# axiom_beta_interface_dummy_v0_9.net
KiCad netlist of a schematic drawn in EAGLE
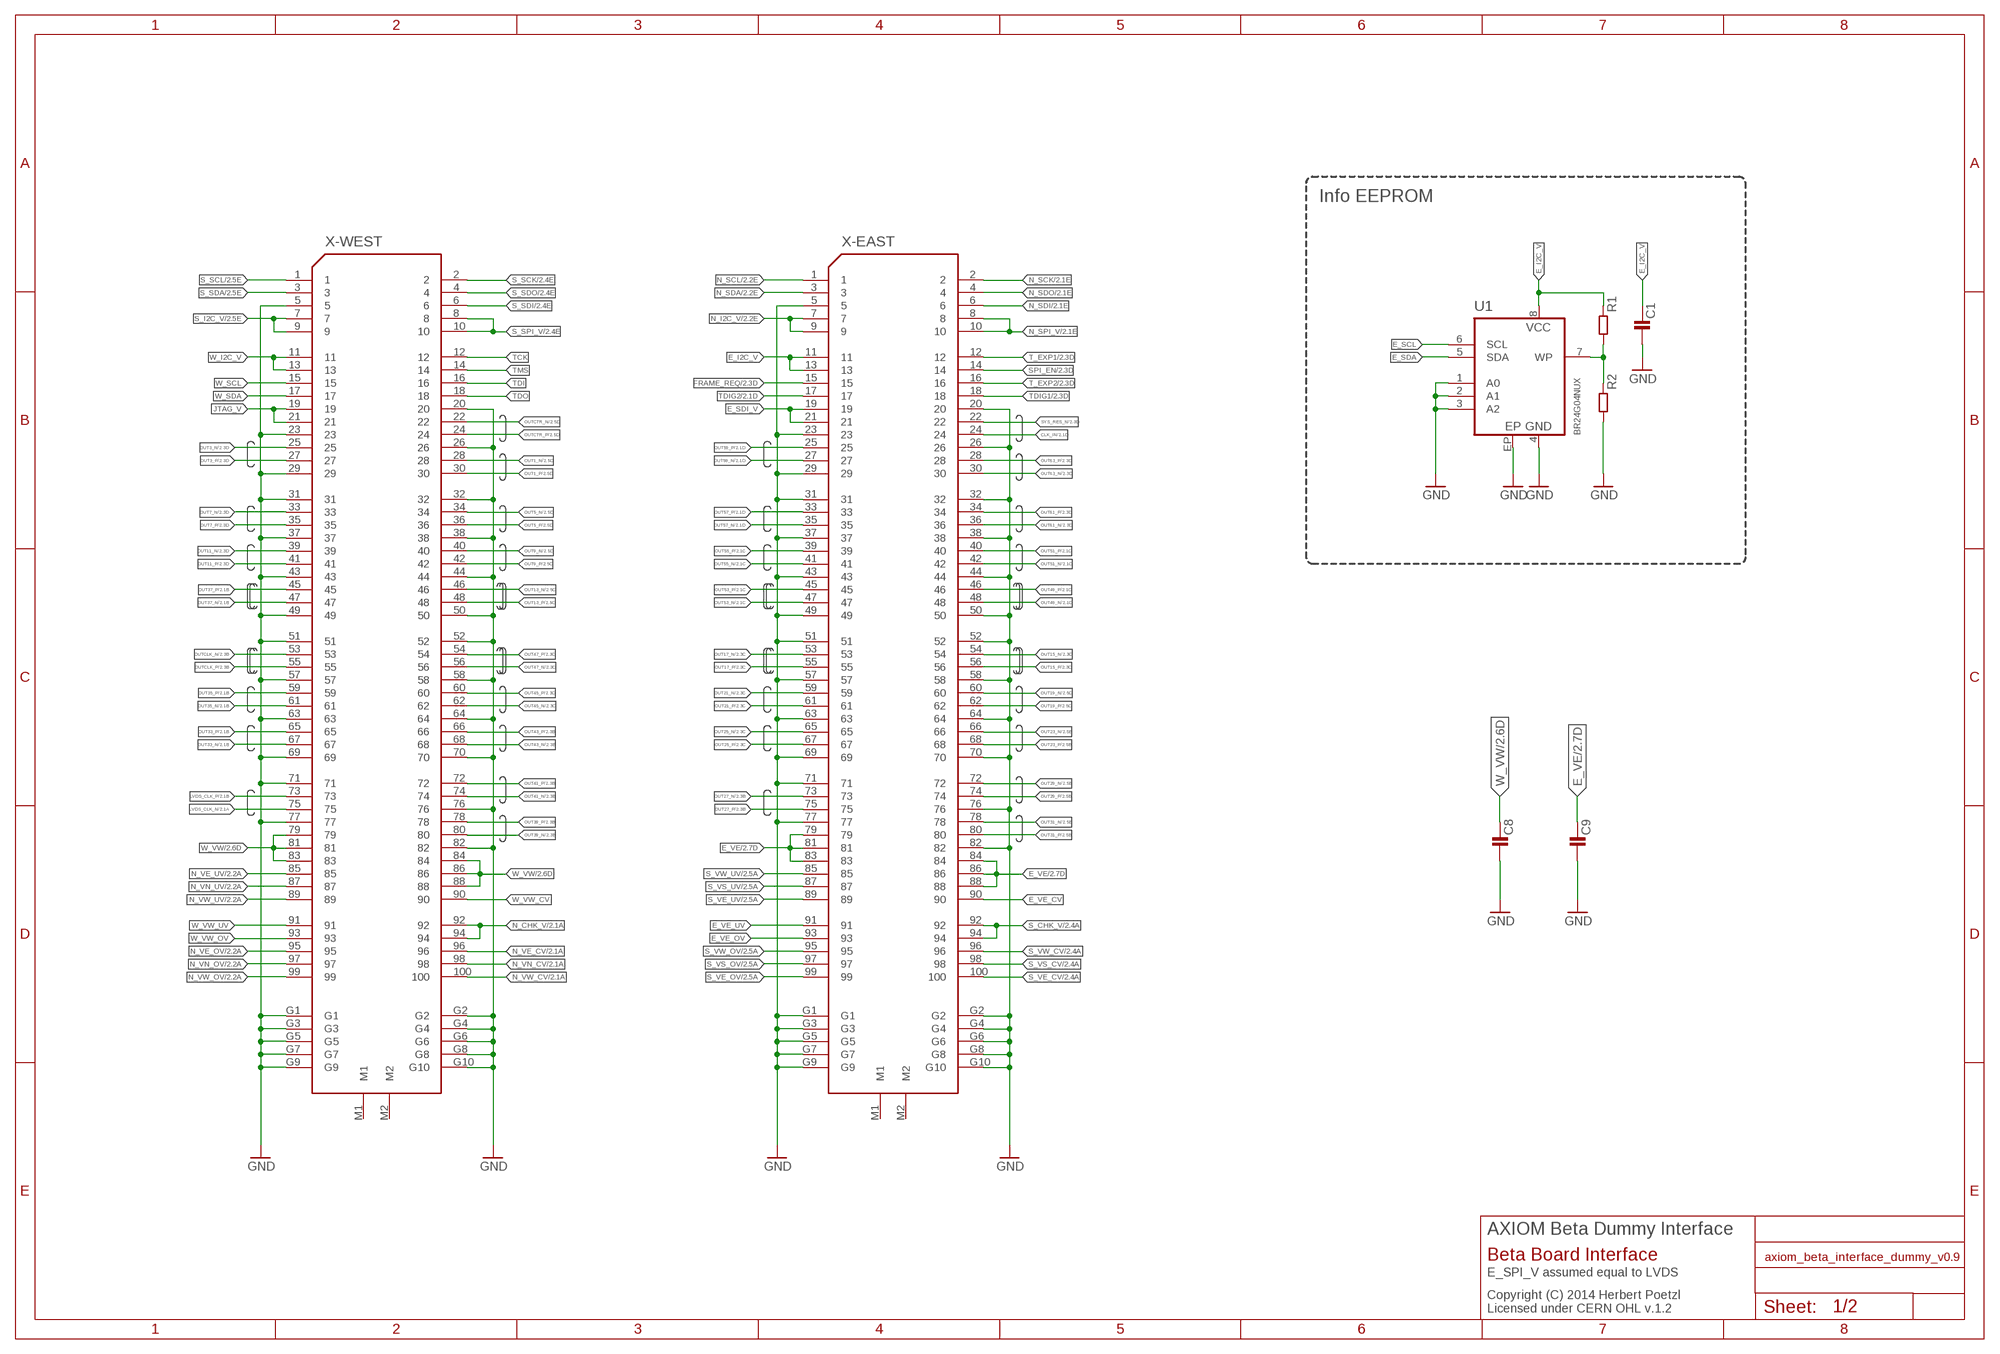
[diagram p0: schematic, sheet 1]
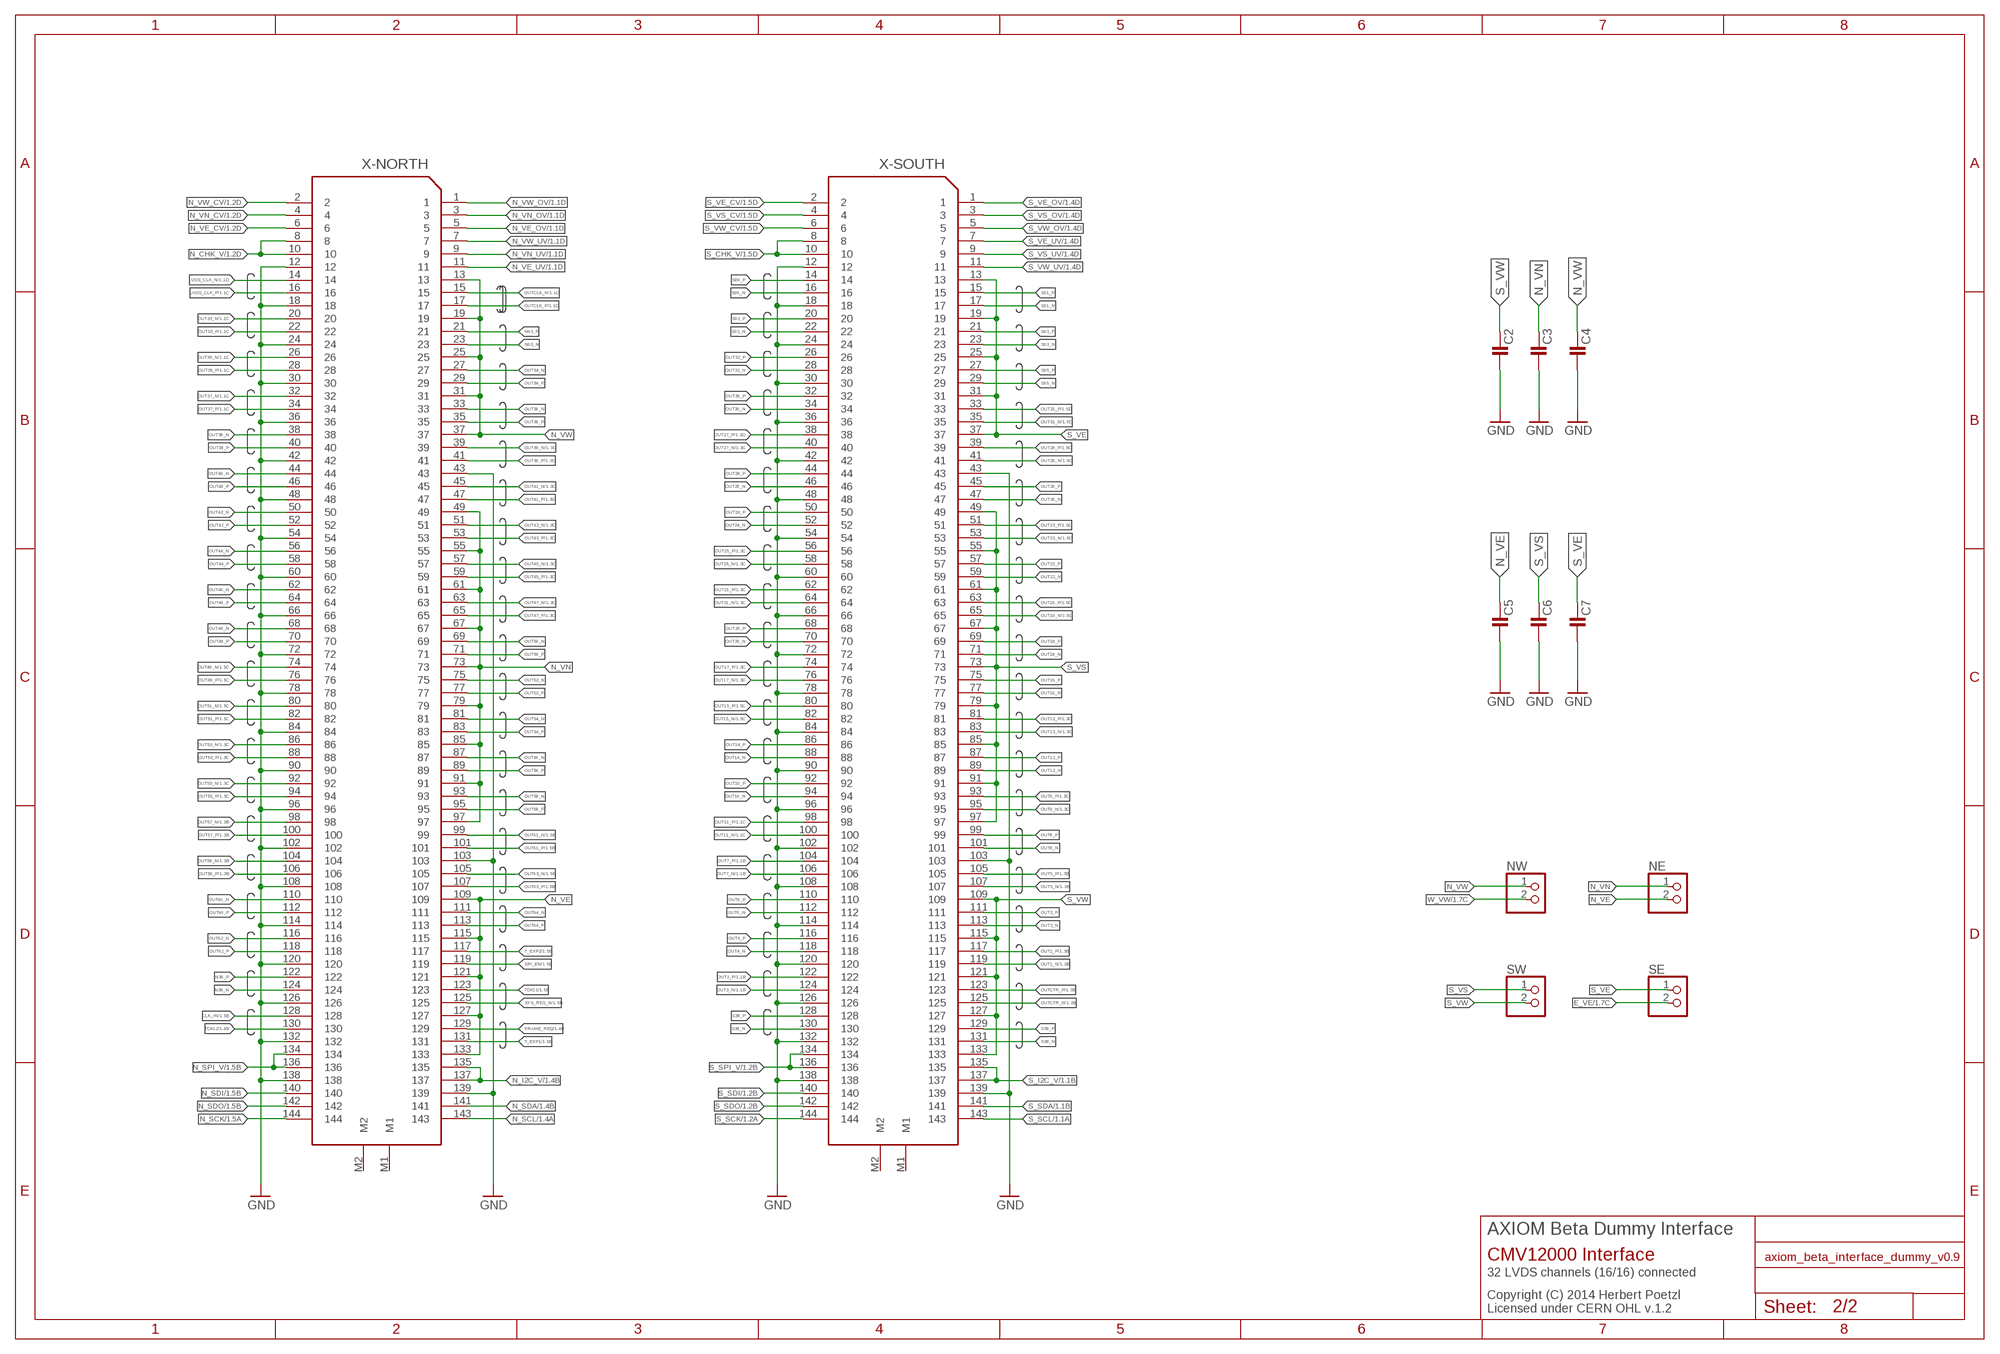
[diagram p1: schematic, sheet 2]

(export (version "E")
  (design (tool "Eeschema 10.0.6"))
  (components
    (comp (ref "C2")
      (value "C0805-B")
      (footprint "eagle-import:0805-B")
      (libsource (lib "eagle-import") (part "C0805-B"))
    )
    (comp (ref "C3")
      (value "C0805-B")
      (footprint "eagle-import:0805-B")
      (libsource (lib "eagle-import") (part "C0805-B"))
    )
    (comp (ref "C4")
      (value "C0805-B")
      (footprint "eagle-import:0805-B")
      (libsource (lib "eagle-import") (part "C0805-B"))
    )
    (comp (ref "C5")
      (value "C0805-B")
      (footprint "eagle-import:0805-B")
      (libsource (lib "eagle-import") (part "C0805-B"))
    )
    (comp (ref "C6")
      (value "C0805-B")
      (footprint "eagle-import:0805-B")
      (libsource (lib "eagle-import") (part "C0805-B"))
    )
    (comp (ref "C7")
      (value "C0805-B")
      (footprint "eagle-import:0805-B")
      (libsource (lib "eagle-import") (part "C0805-B"))
    )
    (comp (ref "NE")
      (value "PINHD-1X02_2.54")
      (footprint "eagle-import:1X02")
      (libsource (lib "eagle-import") (part "PINHD-1X02_2.54"))
    )
    (comp (ref "NW")
      (value "PINHD-1X02_2.54")
      (footprint "eagle-import:1X02")
      (libsource (lib "eagle-import") (part "PINHD-1X02_2.54"))
    )
    (comp (ref "SE")
      (value "PINHD-1X02_2.54")
      (footprint "eagle-import:1X02")
      (libsource (lib "eagle-import") (part "PINHD-1X02_2.54"))
    )
    (comp (ref "SW")
      (value "PINHD-1X02_2.54")
      (footprint "eagle-import:1X02")
      (libsource (lib "eagle-import") (part "PINHD-1X02_2.54"))
    )
    (comp (ref "X-NORTH")
      (value "FX10-144S")
      (footprint "eagle-import:FX10A-144S")
      (libsource (lib "eagle-import") (part "FX10-144S"))
    )
    (comp (ref "X-SOUTH")
      (value "FX10-144S")
      (footprint "eagle-import:FX10A-144S")
      (libsource (lib "eagle-import") (part "FX10-144S"))
    )
    (comp (ref "C1")
      (value "C0402-B")
      (footprint "eagle-import:0402-B")
      (libsource (lib "eagle-import") (part "C0402-B"))
    )
    (comp (ref "C8")
      (value "C0805-B")
      (footprint "eagle-import:0805-B")
      (libsource (lib "eagle-import") (part "C0805-B"))
    )
    (comp (ref "C9")
      (value "C0805-B")
      (footprint "eagle-import:0805-B")
      (libsource (lib "eagle-import") (part "C0805-B"))
    )
    (comp (ref "R1")
      (value "R0402-B")
      (footprint "eagle-import:0402-B")
      (libsource (lib "eagle-import") (part "R0402-B"))
    )
    (comp (ref "R2")
      (value "R0402-B")
      (footprint "eagle-import:0402-B")
      (libsource (lib "eagle-import") (part "R0402-B"))
    )
    (comp (ref "U1")
      (value "BR24G04NUX")
      (footprint "eagle-import:DFN200X300X100-9N")
      (libsource (lib "eagle-import") (part "BR24G04NUX"))
    )
    (comp (ref "X-EAST")
      (value "FX10-100/10P")
      (footprint "eagle-import:FX10A-100P_10")
      (libsource (lib "eagle-import") (part "FX10-100/10P"))
    )
    (comp (ref "X-WEST")
      (value "FX10-100/10P")
      (footprint "eagle-import:FX10A-100P_10")
      (libsource (lib "eagle-import") (part "FX10-100/10P"))
    )
  )
  (nets
    (net (code "1") (name "CLK_IN") (class "Default")
      (node (ref "X-EAST") (pin "24") (pinfunction "24_24") (pintype "bidirectional"))
      (node (ref "X-NORTH") (pin "128") (pinfunction "128_128") (pintype "bidirectional"))
    )
    (net (code "2") (name "E_I2C_V") (class "Default")
      (node (ref "C1") (pin "1") (pinfunction "1_1") (pintype "passive"))
      (node (ref "R1") (pin "1") (pinfunction "1_1") (pintype "passive"))
      (node (ref "U1") (pin "8") (pinfunction "VCC_8") (pintype "power_in"))
      (node (ref "X-EAST") (pin "11") (pinfunction "11_11") (pintype "bidirectional"))
      (node (ref "X-EAST") (pin "13") (pinfunction "13_13") (pintype "bidirectional"))
    )
    (net (code "3") (name "E_SCL") (class "Default")
      (node (ref "U1") (pin "6") (pinfunction "SCL_6") (pintype "input"))
    )
    (net (code "4") (name "E_SDA") (class "Default")
      (node (ref "U1") (pin "5") (pinfunction "SDA_5") (pintype "bidirectional"))
    )
    (net (code "5") (name "E_SDI_V") (class "Default")
      (node (ref "X-EAST") (pin "19") (pinfunction "19_19") (pintype "bidirectional"))
      (node (ref "X-EAST") (pin "21") (pinfunction "21_21") (pintype "bidirectional"))
    )
    (net (code "6") (name "E_VE") (class "Default")
      (node (ref "C9") (pin "1") (pinfunction "1_1") (pintype "passive"))
      (node (ref "SE") (pin "2") (pinfunction "2_2") (pintype "passive"))
      (node (ref "X-EAST") (pin "79") (pinfunction "79_79") (pintype "bidirectional"))
      (node (ref "X-EAST") (pin "81") (pinfunction "81_81") (pintype "bidirectional"))
      (node (ref "X-EAST") (pin "83") (pinfunction "83_83") (pintype "bidirectional"))
      (node (ref "X-EAST") (pin "84") (pinfunction "84_84") (pintype "bidirectional"))
      (node (ref "X-EAST") (pin "86") (pinfunction "86_86") (pintype "bidirectional"))
      (node (ref "X-EAST") (pin "88") (pinfunction "88_88") (pintype "bidirectional"))
    )
    (net (code "7") (name "E_VE_CV") (class "Default")
      (node (ref "X-EAST") (pin "90") (pinfunction "90_90") (pintype "bidirectional"))
    )
    (net (code "8") (name "E_VE_OV") (class "Default")
      (node (ref "X-EAST") (pin "93") (pinfunction "93_93") (pintype "bidirectional"))
    )
    (net (code "9") (name "E_VE_UV") (class "Default")
      (node (ref "X-EAST") (pin "91") (pinfunction "91_91") (pintype "bidirectional"))
    )
    (net (code "10") (name "FRAME_REQ") (class "Default")
      (node (ref "X-EAST") (pin "15") (pinfunction "15_15") (pintype "bidirectional"))
      (node (ref "X-NORTH") (pin "129") (pinfunction "129_129") (pintype "bidirectional"))
    )
    (net (code "11") (name "GND") (class "Default")
      (node (ref "C1") (pin "2") (pinfunction "2_2") (pintype "passive"))
      (node (ref "C2") (pin "2") (pinfunction "2_2") (pintype "passive"))
      (node (ref "C3") (pin "2") (pinfunction "2_2") (pintype "passive"))
      (node (ref "C4") (pin "2") (pinfunction "2_2") (pintype "passive"))
      (node (ref "C5") (pin "2") (pinfunction "2_2") (pintype "passive"))
      (node (ref "C6") (pin "2") (pinfunction "2_2") (pintype "passive"))
      (node (ref "C7") (pin "2") (pinfunction "2_2") (pintype "passive"))
      (node (ref "C8") (pin "2") (pinfunction "2_2") (pintype "passive"))
      (node (ref "C9") (pin "2") (pinfunction "2_2") (pintype "passive"))
      (node (ref "R2") (pin "2") (pinfunction "2_2") (pintype "passive"))
      (node (ref "U1") (pin "1") (pinfunction "A0_1") (pintype "input"))
      (node (ref "U1") (pin "2") (pinfunction "A1_2") (pintype "input"))
      (node (ref "U1") (pin "3") (pinfunction "A2_3") (pintype "input"))
      (node (ref "U1") (pin "4") (pinfunction "GND_4") (pintype "passive"))
      (node (ref "U1") (pin "EP") (pinfunction "EP_EP") (pintype "passive"))
      (node (ref "X-EAST") (pin "20") (pinfunction "20_20") (pintype "bidirectional"))
      (node (ref "X-EAST") (pin "23") (pinfunction "23_23") (pintype "bidirectional"))
      (node (ref "X-EAST") (pin "26") (pinfunction "26_26") (pintype "bidirectional"))
      (node (ref "X-EAST") (pin "29") (pinfunction "29_29") (pintype "bidirectional"))
      (node (ref "X-EAST") (pin "31") (pinfunction "31_31") (pintype "bidirectional"))
      (node (ref "X-EAST") (pin "32") (pinfunction "32_32") (pintype "bidirectional"))
      (node (ref "X-EAST") (pin "37") (pinfunction "37_37") (pintype "bidirectional"))
      (node (ref "X-EAST") (pin "38") (pinfunction "38_38") (pintype "bidirectional"))
      (node (ref "X-EAST") (pin "43") (pinfunction "43_43") (pintype "bidirectional"))
      (node (ref "X-EAST") (pin "44") (pinfunction "44_44") (pintype "bidirectional"))
      (node (ref "X-EAST") (pin "49") (pinfunction "49_49") (pintype "bidirectional"))
      (node (ref "X-EAST") (pin "5") (pinfunction "5_5") (pintype "bidirectional"))
      (node (ref "X-EAST") (pin "50") (pinfunction "50_50") (pintype "bidirectional"))
      (node (ref "X-EAST") (pin "51") (pinfunction "51_51") (pintype "bidirectional"))
      (node (ref "X-EAST") (pin "52") (pinfunction "52_52") (pintype "bidirectional"))
      (node (ref "X-EAST") (pin "57") (pinfunction "57_57") (pintype "bidirectional"))
      (node (ref "X-EAST") (pin "58") (pinfunction "58_58") (pintype "bidirectional"))
      (node (ref "X-EAST") (pin "63") (pinfunction "63_63") (pintype "bidirectional"))
      (node (ref "X-EAST") (pin "64") (pinfunction "64_64") (pintype "bidirectional"))
      (node (ref "X-EAST") (pin "69") (pinfunction "69_69") (pintype "bidirectional"))
      (node (ref "X-EAST") (pin "70") (pinfunction "70_70") (pintype "bidirectional"))
      (node (ref "X-EAST") (pin "71") (pinfunction "71_71") (pintype "bidirectional"))
      (node (ref "X-EAST") (pin "76") (pinfunction "76_76") (pintype "bidirectional"))
      (node (ref "X-EAST") (pin "77") (pinfunction "77_77") (pintype "bidirectional"))
      (node (ref "X-EAST") (pin "82") (pinfunction "82_82") (pintype "bidirectional"))
      (node (ref "X-EAST") (pin "G1") (pinfunction "G1_G1") (pintype "bidirectional"))
      (node (ref "X-EAST") (pin "G10") (pinfunction "G10_G10") (pintype "bidirectional"))
      (node (ref "X-EAST") (pin "G2") (pinfunction "G2_G2") (pintype "bidirectional"))
      (node (ref "X-EAST") (pin "G3") (pinfunction "G3_G3") (pintype "bidirectional"))
      (node (ref "X-EAST") (pin "G4") (pinfunction "G4_G4") (pintype "bidirectional"))
      (node (ref "X-EAST") (pin "G5") (pinfunction "G5_G5") (pintype "bidirectional"))
      (node (ref "X-EAST") (pin "G6") (pinfunction "G6_G6") (pintype "bidirectional"))
      (node (ref "X-EAST") (pin "G7") (pinfunction "G7_G7") (pintype "bidirectional"))
      (node (ref "X-EAST") (pin "G8") (pinfunction "G8_G8") (pintype "bidirectional"))
      (node (ref "X-EAST") (pin "G9") (pinfunction "G9_G9") (pintype "bidirectional"))
      (node (ref "X-NORTH") (pin "102") (pinfunction "102_102") (pintype "bidirectional"))
      (node (ref "X-NORTH") (pin "103") (pinfunction "103_103") (pintype "bidirectional"))
      (node (ref "X-NORTH") (pin "108") (pinfunction "108_108") (pintype "bidirectional"))
      (node (ref "X-NORTH") (pin "114") (pinfunction "114_114") (pintype "bidirectional"))
      (node (ref "X-NORTH") (pin "12") (pinfunction "12_12") (pintype "bidirectional"))
      (node (ref "X-NORTH") (pin "120") (pinfunction "120_120") (pintype "bidirectional"))
      (node (ref "X-NORTH") (pin "126") (pinfunction "126_126") (pintype "bidirectional"))
      (node (ref "X-NORTH") (pin "132") (pinfunction "132_132") (pintype "bidirectional"))
      (node (ref "X-NORTH") (pin "138") (pinfunction "138_138") (pintype "bidirectional"))
      (node (ref "X-NORTH") (pin "139") (pinfunction "139_139") (pintype "bidirectional"))
      (node (ref "X-NORTH") (pin "18") (pinfunction "18_18") (pintype "bidirectional"))
      (node (ref "X-NORTH") (pin "24") (pinfunction "24_24") (pintype "bidirectional"))
      (node (ref "X-NORTH") (pin "30") (pinfunction "30_30") (pintype "bidirectional"))
      (node (ref "X-NORTH") (pin "36") (pinfunction "36_36") (pintype "bidirectional"))
      (node (ref "X-NORTH") (pin "42") (pinfunction "42_42") (pintype "bidirectional"))
      (node (ref "X-NORTH") (pin "43") (pinfunction "43_43") (pintype "bidirectional"))
      (node (ref "X-NORTH") (pin "48") (pinfunction "48_48") (pintype "bidirectional"))
      (node (ref "X-NORTH") (pin "54") (pinfunction "54_54") (pintype "bidirectional"))
      (node (ref "X-NORTH") (pin "60") (pinfunction "60_60") (pintype "bidirectional"))
      (node (ref "X-NORTH") (pin "66") (pinfunction "66_66") (pintype "bidirectional"))
      (node (ref "X-NORTH") (pin "72") (pinfunction "72_72") (pintype "bidirectional"))
      (node (ref "X-NORTH") (pin "78") (pinfunction "78_78") (pintype "bidirectional"))
      (node (ref "X-NORTH") (pin "84") (pinfunction "84_84") (pintype "bidirectional"))
      (node (ref "X-NORTH") (pin "90") (pinfunction "90_90") (pintype "bidirectional"))
      (node (ref "X-NORTH") (pin "96") (pinfunction "96_96") (pintype "bidirectional"))
      (node (ref "X-SOUTH") (pin "102") (pinfunction "102_102") (pintype "bidirectional"))
      (node (ref "X-SOUTH") (pin "103") (pinfunction "103_103") (pintype "bidirectional"))
      (node (ref "X-SOUTH") (pin "108") (pinfunction "108_108") (pintype "bidirectional"))
      (node (ref "X-SOUTH") (pin "114") (pinfunction "114_114") (pintype "bidirectional"))
      (node (ref "X-SOUTH") (pin "12") (pinfunction "12_12") (pintype "bidirectional"))
      (node (ref "X-SOUTH") (pin "120") (pinfunction "120_120") (pintype "bidirectional"))
      (node (ref "X-SOUTH") (pin "126") (pinfunction "126_126") (pintype "bidirectional"))
      (node (ref "X-SOUTH") (pin "132") (pinfunction "132_132") (pintype "bidirectional"))
      (node (ref "X-SOUTH") (pin "138") (pinfunction "138_138") (pintype "bidirectional"))
      (node (ref "X-SOUTH") (pin "139") (pinfunction "139_139") (pintype "bidirectional"))
      (node (ref "X-SOUTH") (pin "18") (pinfunction "18_18") (pintype "bidirectional"))
      (node (ref "X-SOUTH") (pin "24") (pinfunction "24_24") (pintype "bidirectional"))
      (node (ref "X-SOUTH") (pin "30") (pinfunction "30_30") (pintype "bidirectional"))
      (node (ref "X-SOUTH") (pin "36") (pinfunction "36_36") (pintype "bidirectional"))
      (node (ref "X-SOUTH") (pin "42") (pinfunction "42_42") (pintype "bidirectional"))
      (node (ref "X-SOUTH") (pin "43") (pinfunction "43_43") (pintype "bidirectional"))
      (node (ref "X-SOUTH") (pin "48") (pinfunction "48_48") (pintype "bidirectional"))
      (node (ref "X-SOUTH") (pin "54") (pinfunction "54_54") (pintype "bidirectional"))
      (node (ref "X-SOUTH") (pin "60") (pinfunction "60_60") (pintype "bidirectional"))
      (node (ref "X-SOUTH") (pin "66") (pinfunction "66_66") (pintype "bidirectional"))
      (node (ref "X-SOUTH") (pin "72") (pinfunction "72_72") (pintype "bidirectional"))
      (node (ref "X-SOUTH") (pin "78") (pinfunction "78_78") (pintype "bidirectional"))
      (node (ref "X-SOUTH") (pin "84") (pinfunction "84_84") (pintype "bidirectional"))
      (node (ref "X-SOUTH") (pin "90") (pinfunction "90_90") (pintype "bidirectional"))
      (node (ref "X-SOUTH") (pin "96") (pinfunction "96_96") (pintype "bidirectional"))
      (node (ref "X-WEST") (pin "20") (pinfunction "20_20") (pintype "bidirectional"))
      (node (ref "X-WEST") (pin "23") (pinfunction "23_23") (pintype "bidirectional"))
      (node (ref "X-WEST") (pin "26") (pinfunction "26_26") (pintype "bidirectional"))
      (node (ref "X-WEST") (pin "29") (pinfunction "29_29") (pintype "bidirectional"))
      (node (ref "X-WEST") (pin "31") (pinfunction "31_31") (pintype "bidirectional"))
      (node (ref "X-WEST") (pin "32") (pinfunction "32_32") (pintype "bidirectional"))
      (node (ref "X-WEST") (pin "37") (pinfunction "37_37") (pintype "bidirectional"))
      (node (ref "X-WEST") (pin "38") (pinfunction "38_38") (pintype "bidirectional"))
      (node (ref "X-WEST") (pin "43") (pinfunction "43_43") (pintype "bidirectional"))
      (node (ref "X-WEST") (pin "44") (pinfunction "44_44") (pintype "bidirectional"))
      (node (ref "X-WEST") (pin "49") (pinfunction "49_49") (pintype "bidirectional"))
      (node (ref "X-WEST") (pin "5") (pinfunction "5_5") (pintype "bidirectional"))
      (node (ref "X-WEST") (pin "50") (pinfunction "50_50") (pintype "bidirectional"))
      (node (ref "X-WEST") (pin "51") (pinfunction "51_51") (pintype "bidirectional"))
      (node (ref "X-WEST") (pin "52") (pinfunction "52_52") (pintype "bidirectional"))
      (node (ref "X-WEST") (pin "57") (pinfunction "57_57") (pintype "bidirectional"))
      (node (ref "X-WEST") (pin "58") (pinfunction "58_58") (pintype "bidirectional"))
      (node (ref "X-WEST") (pin "63") (pinfunction "63_63") (pintype "bidirectional"))
      (node (ref "X-WEST") (pin "64") (pinfunction "64_64") (pintype "bidirectional"))
      (node (ref "X-WEST") (pin "69") (pinfunction "69_69") (pintype "bidirectional"))
      (node (ref "X-WEST") (pin "70") (pinfunction "70_70") (pintype "bidirectional"))
      (node (ref "X-WEST") (pin "71") (pinfunction "71_71") (pintype "bidirectional"))
      (node (ref "X-WEST") (pin "76") (pinfunction "76_76") (pintype "bidirectional"))
      (node (ref "X-WEST") (pin "77") (pinfunction "77_77") (pintype "bidirectional"))
      (node (ref "X-WEST") (pin "82") (pinfunction "82_82") (pintype "bidirectional"))
      (node (ref "X-WEST") (pin "G1") (pinfunction "G1_G1") (pintype "bidirectional"))
      (node (ref "X-WEST") (pin "G10") (pinfunction "G10_G10") (pintype "bidirectional"))
      (node (ref "X-WEST") (pin "G2") (pinfunction "G2_G2") (pintype "bidirectional"))
      (node (ref "X-WEST") (pin "G3") (pinfunction "G3_G3") (pintype "bidirectional"))
      (node (ref "X-WEST") (pin "G4") (pinfunction "G4_G4") (pintype "bidirectional"))
      (node (ref "X-WEST") (pin "G5") (pinfunction "G5_G5") (pintype "bidirectional"))
      (node (ref "X-WEST") (pin "G6") (pinfunction "G6_G6") (pintype "bidirectional"))
      (node (ref "X-WEST") (pin "G7") (pinfunction "G7_G7") (pintype "bidirectional"))
      (node (ref "X-WEST") (pin "G8") (pinfunction "G8_G8") (pintype "bidirectional"))
      (node (ref "X-WEST") (pin "G9") (pinfunction "G9_G9") (pintype "bidirectional"))
    )
    (net (code "12") (name "JTAG_V") (class "Default")
      (node (ref "X-WEST") (pin "19") (pinfunction "19_19") (pintype "bidirectional"))
      (node (ref "X-WEST") (pin "21") (pinfunction "21_21") (pintype "bidirectional"))
    )
    (net (code "13") (name "LVDS_CLK_N") (class "Default")
      (node (ref "X-NORTH") (pin "14") (pinfunction "14_14") (pintype "bidirectional"))
      (node (ref "X-WEST") (pin "75") (pinfunction "75_75") (pintype "bidirectional"))
    )
    (net (code "14") (name "LVDS_CLK_P") (class "Default")
      (node (ref "X-NORTH") (pin "16") (pinfunction "16_16") (pintype "bidirectional"))
      (node (ref "X-WEST") (pin "73") (pinfunction "73_73") (pintype "bidirectional"))
    )
    (net (code "15") (name "N03_N") (class "Default")
      (node (ref "X-NORTH") (pin "23") (pinfunction "23_23") (pintype "bidirectional"))
    )
    (net (code "16") (name "N03_P") (class "Default")
      (node (ref "X-NORTH") (pin "21") (pinfunction "21_21") (pintype "bidirectional"))
    )
    (net (code "17") (name "N36_N") (class "Default")
      (node (ref "X-NORTH") (pin "124") (pinfunction "124_124") (pintype "bidirectional"))
    )
    (net (code "18") (name "N36_P") (class "Default")
      (node (ref "X-NORTH") (pin "122") (pinfunction "122_122") (pintype "bidirectional"))
    )
    (net (code "19") (name "N_CHK_V") (class "Default")
      (node (ref "X-NORTH") (pin "10") (pinfunction "10_10") (pintype "bidirectional"))
      (node (ref "X-NORTH") (pin "8") (pinfunction "8_8") (pintype "bidirectional"))
      (node (ref "X-WEST") (pin "92") (pinfunction "92_92") (pintype "bidirectional"))
      (node (ref "X-WEST") (pin "94") (pinfunction "94_94") (pintype "bidirectional"))
    )
    (net (code "20") (name "N_I2C_V") (class "Default")
      (node (ref "X-EAST") (pin "7") (pinfunction "7_7") (pintype "bidirectional"))
      (node (ref "X-EAST") (pin "9") (pinfunction "9_9") (pintype "bidirectional"))
      (node (ref "X-NORTH") (pin "135") (pinfunction "135_135") (pintype "bidirectional"))
      (node (ref "X-NORTH") (pin "137") (pinfunction "137_137") (pintype "bidirectional"))
    )
    (net (code "21") (name "N_SCK") (class "Default")
      (node (ref "X-EAST") (pin "2") (pinfunction "2_2") (pintype "bidirectional"))
      (node (ref "X-NORTH") (pin "144") (pinfunction "144_144") (pintype "bidirectional"))
    )
    (net (code "22") (name "N_SCL") (class "Default")
      (node (ref "X-EAST") (pin "1") (pinfunction "1_1") (pintype "bidirectional"))
      (node (ref "X-NORTH") (pin "143") (pinfunction "143_143") (pintype "bidirectional"))
    )
    (net (code "23") (name "N_SDA") (class "Default")
      (node (ref "X-EAST") (pin "3") (pinfunction "3_3") (pintype "bidirectional"))
      (node (ref "X-NORTH") (pin "141") (pinfunction "141_141") (pintype "bidirectional"))
    )
    (net (code "24") (name "N_SDI") (class "Default")
      (node (ref "X-EAST") (pin "6") (pinfunction "6_6") (pintype "bidirectional"))
      (node (ref "X-NORTH") (pin "140") (pinfunction "140_140") (pintype "bidirectional"))
    )
    (net (code "25") (name "N_SDO") (class "Default")
      (node (ref "X-EAST") (pin "4") (pinfunction "4_4") (pintype "bidirectional"))
      (node (ref "X-NORTH") (pin "142") (pinfunction "142_142") (pintype "bidirectional"))
    )
    (net (code "26") (name "N_SPI_V") (class "Default")
      (node (ref "X-EAST") (pin "10") (pinfunction "10_10") (pintype "bidirectional"))
      (node (ref "X-EAST") (pin "8") (pinfunction "8_8") (pintype "bidirectional"))
      (node (ref "X-NORTH") (pin "134") (pinfunction "134_134") (pintype "bidirectional"))
      (node (ref "X-NORTH") (pin "136") (pinfunction "136_136") (pintype "bidirectional"))
    )
    (net (code "27") (name "N_VE") (class "Default")
      (node (ref "C5") (pin "1") (pinfunction "1_1") (pintype "passive"))
      (node (ref "NE") (pin "2") (pinfunction "2_2") (pintype "passive"))
      (node (ref "X-NORTH") (pin "109") (pinfunction "109_109") (pintype "bidirectional"))
      (node (ref "X-NORTH") (pin "115") (pinfunction "115_115") (pintype "bidirectional"))
      (node (ref "X-NORTH") (pin "121") (pinfunction "121_121") (pintype "bidirectional"))
      (node (ref "X-NORTH") (pin "127") (pinfunction "127_127") (pintype "bidirectional"))
      (node (ref "X-NORTH") (pin "133") (pinfunction "133_133") (pintype "bidirectional"))
    )
    (net (code "28") (name "N_VE_CV") (class "Default")
      (node (ref "X-NORTH") (pin "6") (pinfunction "6_6") (pintype "bidirectional"))
      (node (ref "X-WEST") (pin "96") (pinfunction "96_96") (pintype "bidirectional"))
    )
    (net (code "29") (name "N_VE_OV") (class "Default")
      (node (ref "X-NORTH") (pin "5") (pinfunction "5_5") (pintype "bidirectional"))
      (node (ref "X-WEST") (pin "95") (pinfunction "95_95") (pintype "bidirectional"))
    )
    (net (code "30") (name "N_VE_UV") (class "Default")
      (node (ref "X-NORTH") (pin "11") (pinfunction "11_11") (pintype "bidirectional"))
      (node (ref "X-WEST") (pin "85") (pinfunction "85_85") (pintype "bidirectional"))
    )
    (net (code "31") (name "N_VN") (class "Default")
      (node (ref "C3") (pin "1") (pinfunction "1_1") (pintype "passive"))
      (node (ref "NE") (pin "1") (pinfunction "1_1") (pintype "passive"))
      (node (ref "X-NORTH") (pin "49") (pinfunction "49_49") (pintype "bidirectional"))
      (node (ref "X-NORTH") (pin "55") (pinfunction "55_55") (pintype "bidirectional"))
      (node (ref "X-NORTH") (pin "61") (pinfunction "61_61") (pintype "bidirectional"))
      (node (ref "X-NORTH") (pin "67") (pinfunction "67_67") (pintype "bidirectional"))
      (node (ref "X-NORTH") (pin "73") (pinfunction "73_73") (pintype "bidirectional"))
      (node (ref "X-NORTH") (pin "79") (pinfunction "79_79") (pintype "bidirectional"))
      (node (ref "X-NORTH") (pin "85") (pinfunction "85_85") (pintype "bidirectional"))
      (node (ref "X-NORTH") (pin "91") (pinfunction "91_91") (pintype "bidirectional"))
      (node (ref "X-NORTH") (pin "97") (pinfunction "97_97") (pintype "bidirectional"))
    )
    (net (code "32") (name "N_VN_CV") (class "Default")
      (node (ref "X-NORTH") (pin "4") (pinfunction "4_4") (pintype "bidirectional"))
      (node (ref "X-WEST") (pin "98") (pinfunction "98_98") (pintype "bidirectional"))
    )
    (net (code "33") (name "N_VN_OV") (class "Default")
      (node (ref "X-NORTH") (pin "3") (pinfunction "3_3") (pintype "bidirectional"))
      (node (ref "X-WEST") (pin "97") (pinfunction "97_97") (pintype "bidirectional"))
    )
    (net (code "34") (name "N_VN_UV") (class "Default")
      (node (ref "X-NORTH") (pin "9") (pinfunction "9_9") (pintype "bidirectional"))
      (node (ref "X-WEST") (pin "87") (pinfunction "87_87") (pintype "bidirectional"))
    )
    (net (code "35") (name "N_VW") (class "Default")
      (node (ref "C4") (pin "1") (pinfunction "1_1") (pintype "passive"))
      (node (ref "NW") (pin "1") (pinfunction "1_1") (pintype "passive"))
      (node (ref "X-NORTH") (pin "13") (pinfunction "13_13") (pintype "bidirectional"))
      (node (ref "X-NORTH") (pin "19") (pinfunction "19_19") (pintype "bidirectional"))
      (node (ref "X-NORTH") (pin "25") (pinfunction "25_25") (pintype "bidirectional"))
      (node (ref "X-NORTH") (pin "31") (pinfunction "31_31") (pintype "bidirectional"))
      (node (ref "X-NORTH") (pin "37") (pinfunction "37_37") (pintype "bidirectional"))
    )
    (net (code "36") (name "N_VW_CV") (class "Default")
      (node (ref "X-NORTH") (pin "2") (pinfunction "2_2") (pintype "bidirectional"))
      (node (ref "X-WEST") (pin "100") (pinfunction "100_100") (pintype "bidirectional"))
    )
    (net (code "37") (name "N_VW_OV") (class "Default")
      (node (ref "X-NORTH") (pin "1") (pinfunction "1_1") (pintype "bidirectional"))
      (node (ref "X-WEST") (pin "99") (pinfunction "99_99") (pintype "bidirectional"))
    )
    (net (code "38") (name "N_VW_UV") (class "Default")
      (node (ref "X-NORTH") (pin "7") (pinfunction "7_7") (pintype "bidirectional"))
      (node (ref "X-WEST") (pin "89") (pinfunction "89_89") (pintype "bidirectional"))
    )
    (net (code "39") (name "Net-(U1-WP)") (class "Default")
      (node (ref "R1") (pin "2") (pinfunction "2_2") (pintype "passive"))
      (node (ref "R2") (pin "1") (pinfunction "1_1") (pintype "passive"))
      (node (ref "U1") (pin "7") (pinfunction "WP_7") (pintype "input"))
    )
    (net (code "40") (name "OUT1_N") (class "Default")
      (node (ref "X-SOUTH") (pin "119") (pinfunction "119_119") (pintype "bidirectional"))
      (node (ref "X-WEST") (pin "28") (pinfunction "28_28") (pintype "bidirectional"))
    )
    (net (code "41") (name "OUT1_P") (class "Default")
      (node (ref "X-SOUTH") (pin "117") (pinfunction "117_117") (pintype "bidirectional"))
      (node (ref "X-WEST") (pin "30") (pinfunction "30_30") (pintype "bidirectional"))
    )
    (net (code "42") (name "OUT2_N") (class "Default")
      (node (ref "X-SOUTH") (pin "113") (pinfunction "113_113") (pintype "bidirectional"))
    )
    (net (code "43") (name "OUT2_P") (class "Default")
      (node (ref "X-SOUTH") (pin "111") (pinfunction "111_111") (pintype "bidirectional"))
    )
    (net (code "44") (name "OUT3_N") (class "Default")
      (node (ref "X-SOUTH") (pin "124") (pinfunction "124_124") (pintype "bidirectional"))
      (node (ref "X-WEST") (pin "25") (pinfunction "25_25") (pintype "bidirectional"))
    )
    (net (code "45") (name "OUT3_P") (class "Default")
      (node (ref "X-SOUTH") (pin "122") (pinfunction "122_122") (pintype "bidirectional"))
      (node (ref "X-WEST") (pin "27") (pinfunction "27_27") (pintype "bidirectional"))
    )
    (net (code "46") (name "OUT4_N") (class "Default")
      (node (ref "X-SOUTH") (pin "118") (pinfunction "118_118") (pintype "bidirectional"))
    )
    (net (code "47") (name "OUT4_P") (class "Default")
      (node (ref "X-SOUTH") (pin "116") (pinfunction "116_116") (pintype "bidirectional"))
    )
    (net (code "48") (name "OUT5_N") (class "Default")
      (node (ref "X-SOUTH") (pin "107") (pinfunction "107_107") (pintype "bidirectional"))
      (node (ref "X-WEST") (pin "34") (pinfunction "34_34") (pintype "bidirectional"))
    )
    (net (code "49") (name "OUT5_P") (class "Default")
      (node (ref "X-SOUTH") (pin "105") (pinfunction "105_105") (pintype "bidirectional"))
      (node (ref "X-WEST") (pin "36") (pinfunction "36_36") (pintype "bidirectional"))
    )
    (net (code "50") (name "OUT6_N") (class "Default")
      (node (ref "X-SOUTH") (pin "112") (pinfunction "112_112") (pintype "bidirectional"))
    )
    (net (code "51") (name "OUT6_P") (class "Default")
      (node (ref "X-SOUTH") (pin "110") (pinfunction "110_110") (pintype "bidirectional"))
    )
    (net (code "52") (name "OUT7_N") (class "Default")
      (node (ref "X-SOUTH") (pin "106") (pinfunction "106_106") (pintype "bidirectional"))
      (node (ref "X-WEST") (pin "33") (pinfunction "33_33") (pintype "bidirectional"))
    )
    (net (code "53") (name "OUT7_P") (class "Default")
      (node (ref "X-SOUTH") (pin "104") (pinfunction "104_104") (pintype "bidirectional"))
      (node (ref "X-WEST") (pin "35") (pinfunction "35_35") (pintype "bidirectional"))
    )
    (net (code "54") (name "OUT8_N") (class "Default")
      (node (ref "X-SOUTH") (pin "101") (pinfunction "101_101") (pintype "bidirectional"))
    )
    (net (code "55") (name "OUT8_P") (class "Default")
      (node (ref "X-SOUTH") (pin "99") (pinfunction "99_99") (pintype "bidirectional"))
    )
    (net (code "56") (name "OUT9_N") (class "Default")
      (node (ref "X-SOUTH") (pin "95") (pinfunction "95_95") (pintype "bidirectional"))
      (node (ref "X-WEST") (pin "40") (pinfunction "40_40") (pintype "bidirectional"))
    )
    (net (code "57") (name "OUT9_P") (class "Default")
      (node (ref "X-SOUTH") (pin "93") (pinfunction "93_93") (pintype "bidirectional"))
      (node (ref "X-WEST") (pin "42") (pinfunction "42_42") (pintype "bidirectional"))
    )
    (net (code "58") (name "OUT10_N") (class "Default")
      (node (ref "X-SOUTH") (pin "94") (pinfunction "94_94") (pintype "bidirectional"))
    )
    (net (code "59") (name "OUT10_P") (class "Default")
      (node (ref "X-SOUTH") (pin "92") (pinfunction "92_92") (pintype "bidirectional"))
    )
    (net (code "60") (name "OUT11_N") (class "Default")
      (node (ref "X-SOUTH") (pin "100") (pinfunction "100_100") (pintype "bidirectional"))
      (node (ref "X-WEST") (pin "39") (pinfunction "39_39") (pintype "bidirectional"))
    )
    (net (code "61") (name "OUT11_P") (class "Default")
      (node (ref "X-SOUTH") (pin "98") (pinfunction "98_98") (pintype "bidirectional"))
      (node (ref "X-WEST") (pin "41") (pinfunction "41_41") (pintype "bidirectional"))
    )
    (net (code "62") (name "OUT12_N") (class "Default")
      (node (ref "X-SOUTH") (pin "89") (pinfunction "89_89") (pintype "bidirectional"))
    )
    (net (code "63") (name "OUT12_P") (class "Default")
      (node (ref "X-SOUTH") (pin "87") (pinfunction "87_87") (pintype "bidirectional"))
    )
    (net (code "64") (name "OUT13_N") (class "Default")
      (node (ref "X-SOUTH") (pin "83") (pinfunction "83_83") (pintype "bidirectional"))
      (node (ref "X-WEST") (pin "46") (pinfunction "46_46") (pintype "bidirectional"))
    )
    (net (code "65") (name "OUT13_P") (class "Default")
      (node (ref "X-SOUTH") (pin "81") (pinfunction "81_81") (pintype "bidirectional"))
      (node (ref "X-WEST") (pin "48") (pinfunction "48_48") (pintype "bidirectional"))
    )
    (net (code "66") (name "OUT14_N") (class "Default")
      (node (ref "X-SOUTH") (pin "88") (pinfunction "88_88") (pintype "bidirectional"))
    )
    (net (code "67") (name "OUT14_P") (class "Default")
      (node (ref "X-SOUTH") (pin "86") (pinfunction "86_86") (pintype "bidirectional"))
    )
    (net (code "68") (name "OUT15_N") (class "Default")
      (node (ref "X-EAST") (pin "54") (pinfunction "54_54") (pintype "bidirectional"))
      (node (ref "X-SOUTH") (pin "82") (pinfunction "82_82") (pintype "bidirectional"))
    )
    (net (code "69") (name "OUT15_P") (class "Default")
      (node (ref "X-EAST") (pin "56") (pinfunction "56_56") (pintype "bidirectional"))
      (node (ref "X-SOUTH") (pin "80") (pinfunction "80_80") (pintype "bidirectional"))
    )
    (net (code "70") (name "OUT16_N") (class "Default")
      (node (ref "X-SOUTH") (pin "77") (pinfunction "77_77") (pintype "bidirectional"))
    )
    (net (code "71") (name "OUT16_P") (class "Default")
      (node (ref "X-SOUTH") (pin "75") (pinfunction "75_75") (pintype "bidirectional"))
    )
    (net (code "72") (name "OUT17_N") (class "Default")
      (node (ref "X-EAST") (pin "53") (pinfunction "53_53") (pintype "bidirectional"))
      (node (ref "X-SOUTH") (pin "76") (pinfunction "76_76") (pintype "bidirectional"))
    )
    (net (code "73") (name "OUT17_P") (class "Default")
      (node (ref "X-EAST") (pin "55") (pinfunction "55_55") (pintype "bidirectional"))
      (node (ref "X-SOUTH") (pin "74") (pinfunction "74_74") (pintype "bidirectional"))
    )
    (net (code "74") (name "OUT18_N") (class "Default")
      (node (ref "X-SOUTH") (pin "71") (pinfunction "71_71") (pintype "bidirectional"))
    )
    (net (code "75") (name "OUT18_P") (class "Default")
      (node (ref "X-SOUTH") (pin "69") (pinfunction "69_69") (pintype "bidirectional"))
    )
    (net (code "76") (name "OUT19_N") (class "Default")
      (node (ref "X-EAST") (pin "60") (pinfunction "60_60") (pintype "bidirectional"))
      (node (ref "X-SOUTH") (pin "65") (pinfunction "65_65") (pintype "bidirectional"))
    )
    (net (code "77") (name "OUT19_P") (class "Default")
      (node (ref "X-EAST") (pin "62") (pinfunction "62_62") (pintype "bidirectional"))
      (node (ref "X-SOUTH") (pin "63") (pinfunction "63_63") (pintype "bidirectional"))
    )
    (net (code "78") (name "OUT20_N") (class "Default")
      (node (ref "X-SOUTH") (pin "70") (pinfunction "70_70") (pintype "bidirectional"))
    )
    (net (code "79") (name "OUT20_P") (class "Default")
      (node (ref "X-SOUTH") (pin "68") (pinfunction "68_68") (pintype "bidirectional"))
    )
    (net (code "80") (name "OUT21_N") (class "Default")
      (node (ref "X-EAST") (pin "59") (pinfunction "59_59") (pintype "bidirectional"))
      (node (ref "X-SOUTH") (pin "64") (pinfunction "64_64") (pintype "bidirectional"))
    )
    (net (code "81") (name "OUT21_P") (class "Default")
      (node (ref "X-EAST") (pin "61") (pinfunction "61_61") (pintype "bidirectional"))
      (node (ref "X-SOUTH") (pin "62") (pinfunction "62_62") (pintype "bidirectional"))
    )
    (net (code "82") (name "OUT22_N") (class "Default")
      (node (ref "X-SOUTH") (pin "59") (pinfunction "59_59") (pintype "bidirectional"))
    )
    (net (code "83") (name "OUT22_P") (class "Default")
      (node (ref "X-SOUTH") (pin "57") (pinfunction "57_57") (pintype "bidirectional"))
    )
    (net (code "84") (name "OUT23_N") (class "Default")
      (node (ref "X-EAST") (pin "66") (pinfunction "66_66") (pintype "bidirectional"))
      (node (ref "X-SOUTH") (pin "53") (pinfunction "53_53") (pintype "bidirectional"))
    )
    (net (code "85") (name "OUT23_P") (class "Default")
      (node (ref "X-EAST") (pin "68") (pinfunction "68_68") (pintype "bidirectional"))
      (node (ref "X-SOUTH") (pin "51") (pinfunction "51_51") (pintype "bidirectional"))
    )
    (net (code "86") (name "OUT24_N") (class "Default")
      (node (ref "X-SOUTH") (pin "52") (pinfunction "52_52") (pintype "bidirectional"))
    )
    (net (code "87") (name "OUT24_P") (class "Default")
      (node (ref "X-SOUTH") (pin "50") (pinfunction "50_50") (pintype "bidirectional"))
    )
    (net (code "88") (name "OUT25_N") (class "Default")
      (node (ref "X-EAST") (pin "65") (pinfunction "65_65") (pintype "bidirectional"))
      (node (ref "X-SOUTH") (pin "58") (pinfunction "58_58") (pintype "bidirectional"))
    )
    (net (code "89") (name "OUT25_P") (class "Default")
      (node (ref "X-EAST") (pin "67") (pinfunction "67_67") (pintype "bidirectional"))
      (node (ref "X-SOUTH") (pin "56") (pinfunction "56_56") (pintype "bidirectional"))
    )
    (net (code "90") (name "OUT26_N") (class "Default")
      (node (ref "X-SOUTH") (pin "47") (pinfunction "47_47") (pintype "bidirectional"))
    )
    (net (code "91") (name "OUT26_P") (class "Default")
      (node (ref "X-SOUTH") (pin "45") (pinfunction "45_45") (pintype "bidirectional"))
    )
    (net (code "92") (name "OUT27_N") (class "Default")
      (node (ref "X-EAST") (pin "73") (pinfunction "73_73") (pintype "bidirectional"))
      (node (ref "X-SOUTH") (pin "40") (pinfunction "40_40") (pintype "bidirectional"))
    )
    (net (code "93") (name "OUT27_P") (class "Default")
      (node (ref "X-EAST") (pin "75") (pinfunction "75_75") (pintype "bidirectional"))
      (node (ref "X-SOUTH") (pin "38") (pinfunction "38_38") (pintype "bidirectional"))
    )
    (net (code "94") (name "OUT28_N") (class "Default")
      (node (ref "X-SOUTH") (pin "46") (pinfunction "46_46") (pintype "bidirectional"))
    )
    (net (code "95") (name "OUT28_P") (class "Default")
      (node (ref "X-SOUTH") (pin "44") (pinfunction "44_44") (pintype "bidirectional"))
    )
    (net (code "96") (name "OUT29_N") (class "Default")
      (node (ref "X-EAST") (pin "72") (pinfunction "72_72") (pintype "bidirectional"))
      (node (ref "X-SOUTH") (pin "41") (pinfunction "41_41") (pintype "bidirectional"))
    )
    (net (code "97") (name "OUT29_P") (class "Default")
      (node (ref "X-EAST") (pin "74") (pinfunction "74_74") (pintype "bidirectional"))
      (node (ref "X-SOUTH") (pin "39") (pinfunction "39_39") (pintype "bidirectional"))
    )
    (net (code "98") (name "OUT30_N") (class "Default")
      (node (ref "X-SOUTH") (pin "34") (pinfunction "34_34") (pintype "bidirectional"))
    )
    (net (code "99") (name "OUT30_P") (class "Default")
      (node (ref "X-SOUTH") (pin "32") (pinfunction "32_32") (pintype "bidirectional"))
    )
    (net (code "100") (name "OUT31_N") (class "Default")
      (node (ref "X-EAST") (pin "78") (pinfunction "78_78") (pintype "bidirectional"))
      (node (ref "X-SOUTH") (pin "35") (pinfunction "35_35") (pintype "bidirectional"))
    )
    (net (code "101") (name "OUT31_P") (class "Default")
      (node (ref "X-EAST") (pin "80") (pinfunction "80_80") (pintype "bidirectional"))
      (node (ref "X-SOUTH") (pin "33") (pinfunction "33_33") (pintype "bidirectional"))
    )
    (net (code "102") (name "OUT32_N") (class "Default")
      (node (ref "X-SOUTH") (pin "28") (pinfunction "28_28") (pintype "bidirectional"))
    )
    (net (code "103") (name "OUT32_P") (class "Default")
      (node (ref "X-SOUTH") (pin "26") (pinfunction "26_26") (pintype "bidirectional"))
    )
    (net (code "104") (name "OUT33_N") (class "Default")
      (node (ref "X-NORTH") (pin "20") (pinfunction "20_20") (pintype "bidirectional"))
      (node (ref "X-WEST") (pin "67") (pinfunction "67_67") (pintype "bidirectional"))
    )
    (net (code "105") (name "OUT33_P") (class "Default")
      (node (ref "X-NORTH") (pin "22") (pinfunction "22_22") (pintype "bidirectional"))
      (node (ref "X-WEST") (pin "65") (pinfunction "65_65") (pintype "bidirectional"))
    )
    (net (code "106") (name "OUT34_N") (class "Default")
      (node (ref "X-NORTH") (pin "27") (pinfunction "27_27") (pintype "bidirectional"))
    )
    (net (code "107") (name "OUT34_P") (class "Default")
      (node (ref "X-NORTH") (pin "29") (pinfunction "29_29") (pintype "bidirectional"))
    )
    (net (code "108") (name "OUT35_N") (class "Default")
      (node (ref "X-NORTH") (pin "26") (pinfunction "26_26") (pintype "bidirectional"))
      (node (ref "X-WEST") (pin "61") (pinfunction "61_61") (pintype "bidirectional"))
    )
    (net (code "109") (name "OUT35_P") (class "Default")
      (node (ref "X-NORTH") (pin "28") (pinfunction "28_28") (pintype "bidirectional"))
      (node (ref "X-WEST") (pin "59") (pinfunction "59_59") (pintype "bidirectional"))
    )
    (net (code "110") (name "OUT36_N") (class "Default")
      (node (ref "X-NORTH") (pin "33") (pinfunction "33_33") (pintype "bidirectional"))
    )
    (net (code "111") (name "OUT36_P") (class "Default")
      (node (ref "X-NORTH") (pin "35") (pinfunction "35_35") (pintype "bidirectional"))
    )
    (net (code "112") (name "OUT37_N") (class "Default")
      (node (ref "X-NORTH") (pin "32") (pinfunction "32_32") (pintype "bidirectional"))
      (node (ref "X-WEST") (pin "47") (pinfunction "47_47") (pintype "bidirectional"))
    )
    (net (code "113") (name "OUT37_P") (class "Default")
      (node (ref "X-NORTH") (pin "34") (pinfunction "34_34") (pintype "bidirectional"))
      (node (ref "X-WEST") (pin "45") (pinfunction "45_45") (pintype "bidirectional"))
    )
    (net (code "114") (name "OUT38_N") (class "Default")
      (node (ref "X-NORTH") (pin "38") (pinfunction "38_38") (pintype "bidirectional"))
    )
    (net (code "115") (name "OUT38_P") (class "Default")
      (node (ref "X-NORTH") (pin "40") (pinfunction "40_40") (pintype "bidirectional"))
    )
    (net (code "116") (name "OUT39_N") (class "Default")
      (node (ref "X-NORTH") (pin "39") (pinfunction "39_39") (pintype "bidirectional"))
      (node (ref "X-WEST") (pin "80") (pinfunction "80_80") (pintype "bidirectional"))
    )
    (net (code "117") (name "OUT39_P") (class "Default")
      (node (ref "X-NORTH") (pin "41") (pinfunction "41_41") (pintype "bidirectional"))
      (node (ref "X-WEST") (pin "78") (pinfunction "78_78") (pintype "bidirectional"))
    )
    (net (code "118") (name "OUT40_N") (class "Default")
      (node (ref "X-NORTH") (pin "44") (pinfunction "44_44") (pintype "bidirectional"))
    )
    (net (code "119") (name "OUT40_P") (class "Default")
      (node (ref "X-NORTH") (pin "46") (pinfunction "46_46") (pintype "bidirectional"))
    )
    (net (code "120") (name "OUT41_N") (class "Default")
      (node (ref "X-NORTH") (pin "45") (pinfunction "45_45") (pintype "bidirectional"))
      (node (ref "X-WEST") (pin "74") (pinfunction "74_74") (pintype "bidirectional"))
    )
    (net (code "121") (name "OUT41_P") (class "Default")
      (node (ref "X-NORTH") (pin "47") (pinfunction "47_47") (pintype "bidirectional"))
      (node (ref "X-WEST") (pin "72") (pinfunction "72_72") (pintype "bidirectional"))
    )
    (net (code "122") (name "OUT42_N") (class "Default")
      (node (ref "X-NORTH") (pin "50") (pinfunction "50_50") (pintype "bidirectional"))
    )
    (net (code "123") (name "OUT42_P") (class "Default")
      (node (ref "X-NORTH") (pin "52") (pinfunction "52_52") (pintype "bidirectional"))
    )
    (net (code "124") (name "OUT43_N") (class "Default")
      (node (ref "X-NORTH") (pin "51") (pinfunction "51_51") (pintype "bidirectional"))
      (node (ref "X-WEST") (pin "68") (pinfunction "68_68") (pintype "bidirectional"))
    )
    (net (code "125") (name "OUT43_P") (class "Default")
      (node (ref "X-NORTH") (pin "53") (pinfunction "53_53") (pintype "bidirectional"))
      (node (ref "X-WEST") (pin "66") (pinfunction "66_66") (pintype "bidirectional"))
    )
    (net (code "126") (name "OUT44_N") (class "Default")
      (node (ref "X-NORTH") (pin "56") (pinfunction "56_56") (pintype "bidirectional"))
    )
    (net (code "127") (name "OUT44_P") (class "Default")
      (node (ref "X-NORTH") (pin "58") (pinfunction "58_58") (pintype "bidirectional"))
    )
    (net (code "128") (name "OUT45_N") (class "Default")
      (node (ref "X-NORTH") (pin "57") (pinfunction "57_57") (pintype "bidirectional"))
      (node (ref "X-WEST") (pin "62") (pinfunction "62_62") (pintype "bidirectional"))
    )
    (net (code "129") (name "OUT45_P") (class "Default")
      (node (ref "X-NORTH") (pin "59") (pinfunction "59_59") (pintype "bidirectional"))
      (node (ref "X-WEST") (pin "60") (pinfunction "60_60") (pintype "bidirectional"))
    )
    (net (code "130") (name "OUT46_N") (class "Default")
      (node (ref "X-NORTH") (pin "62") (pinfunction "62_62") (pintype "bidirectional"))
    )
    (net (code "131") (name "OUT46_P") (class "Default")
      (node (ref "X-NORTH") (pin "64") (pinfunction "64_64") (pintype "bidirectional"))
    )
    (net (code "132") (name "OUT47_N") (class "Default")
      (node (ref "X-NORTH") (pin "63") (pinfunction "63_63") (pintype "bidirectional"))
      (node (ref "X-WEST") (pin "56") (pinfunction "56_56") (pintype "bidirectional"))
    )
    (net (code "133") (name "OUT47_P") (class "Default")
      (node (ref "X-NORTH") (pin "65") (pinfunction "65_65") (pintype "bidirectional"))
      (node (ref "X-WEST") (pin "54") (pinfunction "54_54") (pintype "bidirectional"))
    )
    (net (code "134") (name "OUT48_N") (class "Default")
      (node (ref "X-NORTH") (pin "68") (pinfunction "68_68") (pintype "bidirectional"))
    )
    (net (code "135") (name "OUT48_P") (class "Default")
      (node (ref "X-NORTH") (pin "70") (pinfunction "70_70") (pintype "bidirectional"))
    )
    (net (code "136") (name "OUT49_N") (class "Default")
      (node (ref "X-EAST") (pin "48") (pinfunction "48_48") (pintype "bidirectional"))
      (node (ref "X-NORTH") (pin "74") (pinfunction "74_74") (pintype "bidirectional"))
    )
    (net (code "137") (name "OUT49_P") (class "Default")
      (node (ref "X-EAST") (pin "46") (pinfunction "46_46") (pintype "bidirectional"))
      (node (ref "X-NORTH") (pin "76") (pinfunction "76_76") (pintype "bidirectional"))
    )
    (net (code "138") (name "OUT50_N") (class "Default")
      (node (ref "X-NORTH") (pin "69") (pinfunction "69_69") (pintype "bidirectional"))
    )
    (net (code "139") (name "OUT50_P") (class "Default")
      (node (ref "X-NORTH") (pin "71") (pinfunction "71_71") (pintype "bidirectional"))
    )
    (net (code "140") (name "OUT51_N") (class "Default")
      (node (ref "X-EAST") (pin "42") (pinfunction "42_42") (pintype "bidirectional"))
      (node (ref "X-NORTH") (pin "80") (pinfunction "80_80") (pintype "bidirectional"))
    )
    (net (code "141") (name "OUT51_P") (class "Default")
      (node (ref "X-EAST") (pin "40") (pinfunction "40_40") (pintype "bidirectional"))
      (node (ref "X-NORTH") (pin "82") (pinfunction "82_82") (pintype "bidirectional"))
    )
    (net (code "142") (name "OUT52_N") (class "Default")
      (node (ref "X-NORTH") (pin "75") (pinfunction "75_75") (pintype "bidirectional"))
    )
    (net (code "143") (name "OUT52_P") (class "Default")
      (node (ref "X-NORTH") (pin "77") (pinfunction "77_77") (pintype "bidirectional"))
    )
    (net (code "144") (name "OUT53_N") (class "Default")
      (node (ref "X-EAST") (pin "47") (pinfunction "47_47") (pintype "bidirectional"))
      (node (ref "X-NORTH") (pin "86") (pinfunction "86_86") (pintype "bidirectional"))
    )
    (net (code "145") (name "OUT53_P") (class "Default")
      (node (ref "X-EAST") (pin "45") (pinfunction "45_45") (pintype "bidirectional"))
      (node (ref "X-NORTH") (pin "88") (pinfunction "88_88") (pintype "bidirectional"))
    )
    (net (code "146") (name "OUT54_N") (class "Default")
      (node (ref "X-NORTH") (pin "81") (pinfunction "81_81") (pintype "bidirectional"))
    )
    (net (code "147") (name "OUT54_P") (class "Default")
      (node (ref "X-NORTH") (pin "83") (pinfunction "83_83") (pintype "bidirectional"))
    )
    (net (code "148") (name "OUT55_N") (class "Default")
      (node (ref "X-EAST") (pin "41") (pinfunction "41_41") (pintype "bidirectional"))
      (node (ref "X-NORTH") (pin "92") (pinfunction "92_92") (pintype "bidirectional"))
    )
    (net (code "149") (name "OUT55_P") (class "Default")
      (node (ref "X-EAST") (pin "39") (pinfunction "39_39") (pintype "bidirectional"))
      (node (ref "X-NORTH") (pin "94") (pinfunction "94_94") (pintype "bidirectional"))
    )
    (net (code "150") (name "OUT56_N") (class "Default")
      (node (ref "X-NORTH") (pin "87") (pinfunction "87_87") (pintype "bidirectional"))
    )
    (net (code "151") (name "OUT56_P") (class "Default")
      (node (ref "X-NORTH") (pin "89") (pinfunction "89_89") (pintype "bidirectional"))
    )
    (net (code "152") (name "OUT57_N") (class "Default")
      (node (ref "X-EAST") (pin "35") (pinfunction "35_35") (pintype "bidirectional"))
      (node (ref "X-NORTH") (pin "98") (pinfunction "98_98") (pintype "bidirectional"))
    )
    (net (code "153") (name "OUT57_P") (class "Default")
      (node (ref "X-EAST") (pin "33") (pinfunction "33_33") (pintype "bidirectional"))
      (node (ref "X-NORTH") (pin "100") (pinfunction "100_100") (pintype "bidirectional"))
    )
    (net (code "154") (name "OUT58_N") (class "Default")
      (node (ref "X-NORTH") (pin "93") (pinfunction "93_93") (pintype "bidirectional"))
    )
    (net (code "155") (name "OUT58_P") (class "Default")
      (node (ref "X-NORTH") (pin "95") (pinfunction "95_95") (pintype "bidirectional"))
    )
    (net (code "156") (name "OUT59_N") (class "Default")
      (node (ref "X-EAST") (pin "27") (pinfunction "27_27") (pintype "bidirectional"))
      (node (ref "X-NORTH") (pin "104") (pinfunction "104_104") (pintype "bidirectional"))
    )
    (net (code "157") (name "OUT59_P") (class "Default")
      (node (ref "X-EAST") (pin "25") (pinfunction "25_25") (pintype "bidirectional"))
      (node (ref "X-NORTH") (pin "106") (pinfunction "106_106") (pintype "bidirectional"))
    )
    (net (code "158") (name "OUT60_N") (class "Default")
      (node (ref "X-NORTH") (pin "110") (pinfunction "110_110") (pintype "bidirectional"))
    )
    (net (code "159") (name "OUT60_P") (class "Default")
      (node (ref "X-NORTH") (pin "112") (pinfunction "112_112") (pintype "bidirectional"))
    )
    (net (code "160") (name "OUT61_N") (class "Default")
      (node (ref "X-EAST") (pin "36") (pinfunction "36_36") (pintype "bidirectional"))
      (node (ref "X-NORTH") (pin "99") (pinfunction "99_99") (pintype "bidirectional"))
    )
    (net (code "161") (name "OUT61_P") (class "Default")
      (node (ref "X-EAST") (pin "34") (pinfunction "34_34") (pintype "bidirectional"))
      (node (ref "X-NORTH") (pin "101") (pinfunction "101_101") (pintype "bidirectional"))
    )
    (net (code "162") (name "OUT62_N") (class "Default")
      (node (ref "X-NORTH") (pin "116") (pinfunction "116_116") (pintype "bidirectional"))
    )
    (net (code "163") (name "OUT62_P") (class "Default")
      (node (ref "X-NORTH") (pin "118") (pinfunction "118_118") (pintype "bidirectional"))
    )
    (net (code "164") (name "OUT63_N") (class "Default")
      (node (ref "X-EAST") (pin "30") (pinfunction "30_30") (pintype "bidirectional"))
      (node (ref "X-NORTH") (pin "105") (pinfunction "105_105") (pintype "bidirectional"))
    )
    (net (code "165") (name "OUT63_P") (class "Default")
      (node (ref "X-EAST") (pin "28") (pinfunction "28_28") (pintype "bidirectional"))
      (node (ref "X-NORTH") (pin "107") (pinfunction "107_107") (pintype "bidirectional"))
    )
    (net (code "166") (name "OUT64_N") (class "Default")
      (node (ref "X-NORTH") (pin "111") (pinfunction "111_111") (pintype "bidirectional"))
    )
    (net (code "167") (name "OUT64_P") (class "Default")
      (node (ref "X-NORTH") (pin "113") (pinfunction "113_113") (pintype "bidirectional"))
    )
    (net (code "168") (name "OUTCLK_N") (class "Default")
      (node (ref "X-NORTH") (pin "15") (pinfunction "15_15") (pintype "bidirectional"))
      (node (ref "X-WEST") (pin "53") (pinfunction "53_53") (pintype "bidirectional"))
    )
    (net (code "169") (name "OUTCLK_P") (class "Default")
      (node (ref "X-NORTH") (pin "17") (pinfunction "17_17") (pintype "bidirectional"))
      (node (ref "X-WEST") (pin "55") (pinfunction "55_55") (pintype "bidirectional"))
    )
    (net (code "170") (name "OUTCTR_N") (class "Default")
      (node (ref "X-SOUTH") (pin "125") (pinfunction "125_125") (pintype "bidirectional"))
      (node (ref "X-WEST") (pin "22") (pinfunction "22_22") (pintype "bidirectional"))
    )
    (net (code "171") (name "OUTCTR_P") (class "Default")
      (node (ref "X-SOUTH") (pin "123") (pinfunction "123_123") (pintype "bidirectional"))
      (node (ref "X-WEST") (pin "24") (pinfunction "24_24") (pintype "bidirectional"))
    )
    (net (code "172") (name "S00_N") (class "Default")
      (node (ref "X-SOUTH") (pin "16") (pinfunction "16_16") (pintype "bidirectional"))
    )
    (net (code "173") (name "S00_P") (class "Default")
      (node (ref "X-SOUTH") (pin "14") (pinfunction "14_14") (pintype "bidirectional"))
    )
    (net (code "174") (name "S01_N") (class "Default")
      (node (ref "X-SOUTH") (pin "17") (pinfunction "17_17") (pintype "bidirectional"))
    )
    (net (code "175") (name "S01_P") (class "Default")
      (node (ref "X-SOUTH") (pin "15") (pinfunction "15_15") (pintype "bidirectional"))
    )
    (net (code "176") (name "S02_N") (class "Default")
      (node (ref "X-SOUTH") (pin "22") (pinfunction "22_22") (pintype "bidirectional"))
    )
    (net (code "177") (name "S02_P") (class "Default")
      (node (ref "X-SOUTH") (pin "20") (pinfunction "20_20") (pintype "bidirectional"))
    )
    (net (code "178") (name "S03_N") (class "Default")
      (node (ref "X-SOUTH") (pin "23") (pinfunction "23_23") (pintype "bidirectional"))
    )
    (net (code "179") (name "S03_P") (class "Default")
      (node (ref "X-SOUTH") (pin "21") (pinfunction "21_21") (pintype "bidirectional"))
    )
    (net (code "180") (name "S05_N") (class "Default")
      (node (ref "X-SOUTH") (pin "29") (pinfunction "29_29") (pintype "bidirectional"))
    )
    (net (code "181") (name "S05_P") (class "Default")
      (node (ref "X-SOUTH") (pin "27") (pinfunction "27_27") (pintype "bidirectional"))
    )
    (net (code "182") (name "S38_N") (class "Default")
      (node (ref "X-SOUTH") (pin "130") (pinfunction "130_130") (pintype "bidirectional"))
    )
    (net (code "183") (name "S38_P") (class "Default")
      (node (ref "X-SOUTH") (pin "128") (pinfunction "128_128") (pintype "bidirectional"))
    )
    (net (code "184") (name "S39_N") (class "Default")
      (node (ref "X-SOUTH") (pin "131") (pinfunction "131_131") (pintype "bidirectional"))
    )
    (net (code "185") (name "S39_P") (class "Default")
      (node (ref "X-SOUTH") (pin "129") (pinfunction "129_129") (pintype "bidirectional"))
    )
    (net (code "186") (name "SPI_EN") (class "Default")
      (node (ref "X-EAST") (pin "14") (pinfunction "14_14") (pintype "bidirectional"))
      (node (ref "X-NORTH") (pin "119") (pinfunction "119_119") (pintype "bidirectional"))
    )
    (net (code "187") (name "SYS_RES_N") (class "Default")
      (node (ref "X-EAST") (pin "22") (pinfunction "22_22") (pintype "bidirectional"))
      (node (ref "X-NORTH") (pin "125") (pinfunction "125_125") (pintype "bidirectional"))
    )
    (net (code "188") (name "S_CHK_V") (class "Default")
      (node (ref "X-EAST") (pin "92") (pinfunction "92_92") (pintype "bidirectional"))
      (node (ref "X-EAST") (pin "94") (pinfunction "94_94") (pintype "bidirectional"))
      (node (ref "X-SOUTH") (pin "10") (pinfunction "10_10") (pintype "bidirectional"))
      (node (ref "X-SOUTH") (pin "8") (pinfunction "8_8") (pintype "bidirectional"))
    )
    (net (code "189") (name "S_I2C_V") (class "Default")
      (node (ref "X-SOUTH") (pin "135") (pinfunction "135_135") (pintype "bidirectional"))
      (node (ref "X-SOUTH") (pin "137") (pinfunction "137_137") (pintype "bidirectional"))
      (node (ref "X-WEST") (pin "7") (pinfunction "7_7") (pintype "bidirectional"))
      (node (ref "X-WEST") (pin "9") (pinfunction "9_9") (pintype "bidirectional"))
    )
    (net (code "190") (name "S_SCK") (class "Default")
      (node (ref "X-SOUTH") (pin "144") (pinfunction "144_144") (pintype "bidirectional"))
      (node (ref "X-WEST") (pin "2") (pinfunction "2_2") (pintype "bidirectional"))
    )
    (net (code "191") (name "S_SCL") (class "Default")
      (node (ref "X-SOUTH") (pin "143") (pinfunction "143_143") (pintype "bidirectional"))
      (node (ref "X-WEST") (pin "1") (pinfunction "1_1") (pintype "bidirectional"))
    )
    (net (code "192") (name "S_SDA") (class "Default")
      (node (ref "X-SOUTH") (pin "141") (pinfunction "141_141") (pintype "bidirectional"))
      (node (ref "X-WEST") (pin "3") (pinfunction "3_3") (pintype "bidirectional"))
    )
    (net (code "193") (name "S_SDI") (class "Default")
      (node (ref "X-SOUTH") (pin "140") (pinfunction "140_140") (pintype "bidirectional"))
      (node (ref "X-WEST") (pin "6") (pinfunction "6_6") (pintype "bidirectional"))
    )
    (net (code "194") (name "S_SDO") (class "Default")
      (node (ref "X-SOUTH") (pin "142") (pinfunction "142_142") (pintype "bidirectional"))
      (node (ref "X-WEST") (pin "4") (pinfunction "4_4") (pintype "bidirectional"))
    )
    (net (code "195") (name "S_SPI_V") (class "Default")
      (node (ref "X-SOUTH") (pin "134") (pinfunction "134_134") (pintype "bidirectional"))
      (node (ref "X-SOUTH") (pin "136") (pinfunction "136_136") (pintype "bidirectional"))
      (node (ref "X-WEST") (pin "10") (pinfunction "10_10") (pintype "bidirectional"))
      (node (ref "X-WEST") (pin "8") (pinfunction "8_8") (pintype "bidirectional"))
    )
    (net (code "196") (name "S_VE") (class "Default")
      (node (ref "C7") (pin "1") (pinfunction "1_1") (pintype "passive"))
      (node (ref "SE") (pin "1") (pinfunction "1_1") (pintype "passive"))
      (node (ref "X-SOUTH") (pin "13") (pinfunction "13_13") (pintype "bidirectional"))
      (node (ref "X-SOUTH") (pin "19") (pinfunction "19_19") (pintype "bidirectional"))
      (node (ref "X-SOUTH") (pin "25") (pinfunction "25_25") (pintype "bidirectional"))
      (node (ref "X-SOUTH") (pin "31") (pinfunction "31_31") (pintype "bidirectional"))
      (node (ref "X-SOUTH") (pin "37") (pinfunction "37_37") (pintype "bidirectional"))
    )
    (net (code "197") (name "S_VE_CV") (class "Default")
      (node (ref "X-EAST") (pin "100") (pinfunction "100_100") (pintype "bidirectional"))
      (node (ref "X-SOUTH") (pin "2") (pinfunction "2_2") (pintype "bidirectional"))
    )
    (net (code "198") (name "S_VE_OV") (class "Default")
      (node (ref "X-EAST") (pin "99") (pinfunction "99_99") (pintype "bidirectional"))
      (node (ref "X-SOUTH") (pin "1") (pinfunction "1_1") (pintype "bidirectional"))
    )
    (net (code "199") (name "S_VE_UV") (class "Default")
      (node (ref "X-EAST") (pin "89") (pinfunction "89_89") (pintype "bidirectional"))
      (node (ref "X-SOUTH") (pin "7") (pinfunction "7_7") (pintype "bidirectional"))
    )
    (net (code "200") (name "S_VS") (class "Default")
      (node (ref "C6") (pin "1") (pinfunction "1_1") (pintype "passive"))
      (node (ref "SW") (pin "1") (pinfunction "1_1") (pintype "passive"))
      (node (ref "X-SOUTH") (pin "49") (pinfunction "49_49") (pintype "bidirectional"))
      (node (ref "X-SOUTH") (pin "55") (pinfunction "55_55") (pintype "bidirectional"))
      (node (ref "X-SOUTH") (pin "61") (pinfunction "61_61") (pintype "bidirectional"))
      (node (ref "X-SOUTH") (pin "67") (pinfunction "67_67") (pintype "bidirectional"))
      (node (ref "X-SOUTH") (pin "73") (pinfunction "73_73") (pintype "bidirectional"))
      (node (ref "X-SOUTH") (pin "79") (pinfunction "79_79") (pintype "bidirectional"))
      (node (ref "X-SOUTH") (pin "85") (pinfunction "85_85") (pintype "bidirectional"))
      (node (ref "X-SOUTH") (pin "91") (pinfunction "91_91") (pintype "bidirectional"))
      (node (ref "X-SOUTH") (pin "97") (pinfunction "97_97") (pintype "bidirectional"))
    )
    (net (code "201") (name "S_VS_CV") (class "Default")
      (node (ref "X-EAST") (pin "98") (pinfunction "98_98") (pintype "bidirectional"))
      (node (ref "X-SOUTH") (pin "4") (pinfunction "4_4") (pintype "bidirectional"))
    )
    (net (code "202") (name "S_VS_OV") (class "Default")
      (node (ref "X-EAST") (pin "97") (pinfunction "97_97") (pintype "bidirectional"))
      (node (ref "X-SOUTH") (pin "3") (pinfunction "3_3") (pintype "bidirectional"))
    )
    (net (code "203") (name "S_VS_UV") (class "Default")
      (node (ref "X-EAST") (pin "87") (pinfunction "87_87") (pintype "bidirectional"))
      (node (ref "X-SOUTH") (pin "9") (pinfunction "9_9") (pintype "bidirectional"))
    )
    (net (code "204") (name "S_VW") (class "Default")
      (node (ref "C2") (pin "1") (pinfunction "1_1") (pintype "passive"))
      (node (ref "SW") (pin "2") (pinfunction "2_2") (pintype "passive"))
      (node (ref "X-SOUTH") (pin "109") (pinfunction "109_109") (pintype "bidirectional"))
      (node (ref "X-SOUTH") (pin "115") (pinfunction "115_115") (pintype "bidirectional"))
      (node (ref "X-SOUTH") (pin "121") (pinfunction "121_121") (pintype "bidirectional"))
      (node (ref "X-SOUTH") (pin "127") (pinfunction "127_127") (pintype "bidirectional"))
      (node (ref "X-SOUTH") (pin "133") (pinfunction "133_133") (pintype "bidirectional"))
    )
    (net (code "205") (name "S_VW_CV") (class "Default")
      (node (ref "X-EAST") (pin "96") (pinfunction "96_96") (pintype "bidirectional"))
      (node (ref "X-SOUTH") (pin "6") (pinfunction "6_6") (pintype "bidirectional"))
    )
    (net (code "206") (name "S_VW_OV") (class "Default")
      (node (ref "X-EAST") (pin "95") (pinfunction "95_95") (pintype "bidirectional"))
      (node (ref "X-SOUTH") (pin "5") (pinfunction "5_5") (pintype "bidirectional"))
    )
    (net (code "207") (name "S_VW_UV") (class "Default")
      (node (ref "X-EAST") (pin "85") (pinfunction "85_85") (pintype "bidirectional"))
      (node (ref "X-SOUTH") (pin "11") (pinfunction "11_11") (pintype "bidirectional"))
    )
    (net (code "208") (name "TCK") (class "Default")
      (node (ref "X-WEST") (pin "12") (pinfunction "12_12") (pintype "bidirectional"))
    )
    (net (code "209") (name "TDI") (class "Default")
      (node (ref "X-WEST") (pin "16") (pinfunction "16_16") (pintype "bidirectional"))
    )
    (net (code "210") (name "TDIG1") (class "Default")
      (node (ref "X-EAST") (pin "18") (pinfunction "18_18") (pintype "bidirectional"))
      (node (ref "X-NORTH") (pin "123") (pinfunction "123_123") (pintype "bidirectional"))
    )
    (net (code "211") (name "TDIG2") (class "Default")
      (node (ref "X-EAST") (pin "17") (pinfunction "17_17") (pintype "bidirectional"))
      (node (ref "X-NORTH") (pin "130") (pinfunction "130_130") (pintype "bidirectional"))
    )
    (net (code "212") (name "TDO") (class "Default")
      (node (ref "X-WEST") (pin "18") (pinfunction "18_18") (pintype "bidirectional"))
    )
    (net (code "213") (name "TMS") (class "Default")
      (node (ref "X-WEST") (pin "14") (pinfunction "14_14") (pintype "bidirectional"))
    )
    (net (code "214") (name "T_EXP1") (class "Default")
      (node (ref "X-EAST") (pin "12") (pinfunction "12_12") (pintype "bidirectional"))
      (node (ref "X-NORTH") (pin "131") (pinfunction "131_131") (pintype "bidirectional"))
    )
    (net (code "215") (name "T_EXP2") (class "Default")
      (node (ref "X-EAST") (pin "16") (pinfunction "16_16") (pintype "bidirectional"))
      (node (ref "X-NORTH") (pin "117") (pinfunction "117_117") (pintype "bidirectional"))
    )
    (net (code "216") (name "W_I2C_V") (class "Default")
      (node (ref "X-WEST") (pin "11") (pinfunction "11_11") (pintype "bidirectional"))
      (node (ref "X-WEST") (pin "13") (pinfunction "13_13") (pintype "bidirectional"))
    )
    (net (code "217") (name "W_SCL") (class "Default")
      (node (ref "X-WEST") (pin "15") (pinfunction "15_15") (pintype "bidirectional"))
    )
    (net (code "218") (name "W_SDA") (class "Default")
      (node (ref "X-WEST") (pin "17") (pinfunction "17_17") (pintype "bidirectional"))
    )
    (net (code "219") (name "W_VW") (class "Default")
      (node (ref "C8") (pin "1") (pinfunction "1_1") (pintype "passive"))
      (node (ref "NW") (pin "2") (pinfunction "2_2") (pintype "passive"))
      (node (ref "X-WEST") (pin "79") (pinfunction "79_79") (pintype "bidirectional"))
      (node (ref "X-WEST") (pin "81") (pinfunction "81_81") (pintype "bidirectional"))
      (node (ref "X-WEST") (pin "83") (pinfunction "83_83") (pintype "bidirectional"))
      (node (ref "X-WEST") (pin "84") (pinfunction "84_84") (pintype "bidirectional"))
      (node (ref "X-WEST") (pin "86") (pinfunction "86_86") (pintype "bidirectional"))
      (node (ref "X-WEST") (pin "88") (pinfunction "88_88") (pintype "bidirectional"))
    )
    (net (code "220") (name "W_VW_CV") (class "Default")
      (node (ref "X-WEST") (pin "90") (pinfunction "90_90") (pintype "bidirectional"))
    )
    (net (code "221") (name "W_VW_OV") (class "Default")
      (node (ref "X-WEST") (pin "93") (pinfunction "93_93") (pintype "bidirectional"))
    )
    (net (code "222") (name "W_VW_UV") (class "Default")
      (node (ref "X-WEST") (pin "91") (pinfunction "91_91") (pintype "bidirectional"))
    )
    (net (code "223") (name "unconnected-(X-EAST-PadM1)") (class "Default")
      (node (ref "X-EAST") (pin "M1") (pinfunction "M1_M1") (pintype "bidirectional"))
    )
    (net (code "224") (name "unconnected-(X-EAST-PadM2)") (class "Default")
      (node (ref "X-EAST") (pin "M2") (pinfunction "M2_M2") (pintype "bidirectional"))
    )
    (net (code "225") (name "unconnected-(X-NORTH-PadM1)") (class "Default")
      (node (ref "X-NORTH") (pin "M1") (pinfunction "M1_M1") (pintype "bidirectional"))
    )
    (net (code "226") (name "unconnected-(X-NORTH-PadM2)") (class "Default")
      (node (ref "X-NORTH") (pin "M2") (pinfunction "M2_M2") (pintype "bidirectional"))
    )
    (net (code "227") (name "unconnected-(X-SOUTH-PadM1)") (class "Default")
      (node (ref "X-SOUTH") (pin "M1") (pinfunction "M1_M1") (pintype "bidirectional"))
    )
    (net (code "228") (name "unconnected-(X-SOUTH-PadM2)") (class "Default")
      (node (ref "X-SOUTH") (pin "M2") (pinfunction "M2_M2") (pintype "bidirectional"))
    )
    (net (code "229") (name "unconnected-(X-WEST-PadM1)") (class "Default")
      (node (ref "X-WEST") (pin "M1") (pinfunction "M1_M1") (pintype "bidirectional"))
    )
    (net (code "230") (name "unconnected-(X-WEST-PadM2)") (class "Default")
      (node (ref "X-WEST") (pin "M2") (pinfunction "M2_M2") (pintype "bidirectional"))
    )
  )
)
